# Cooling_control.net
KiCad netlist of a schematic drawn in Altium Designer
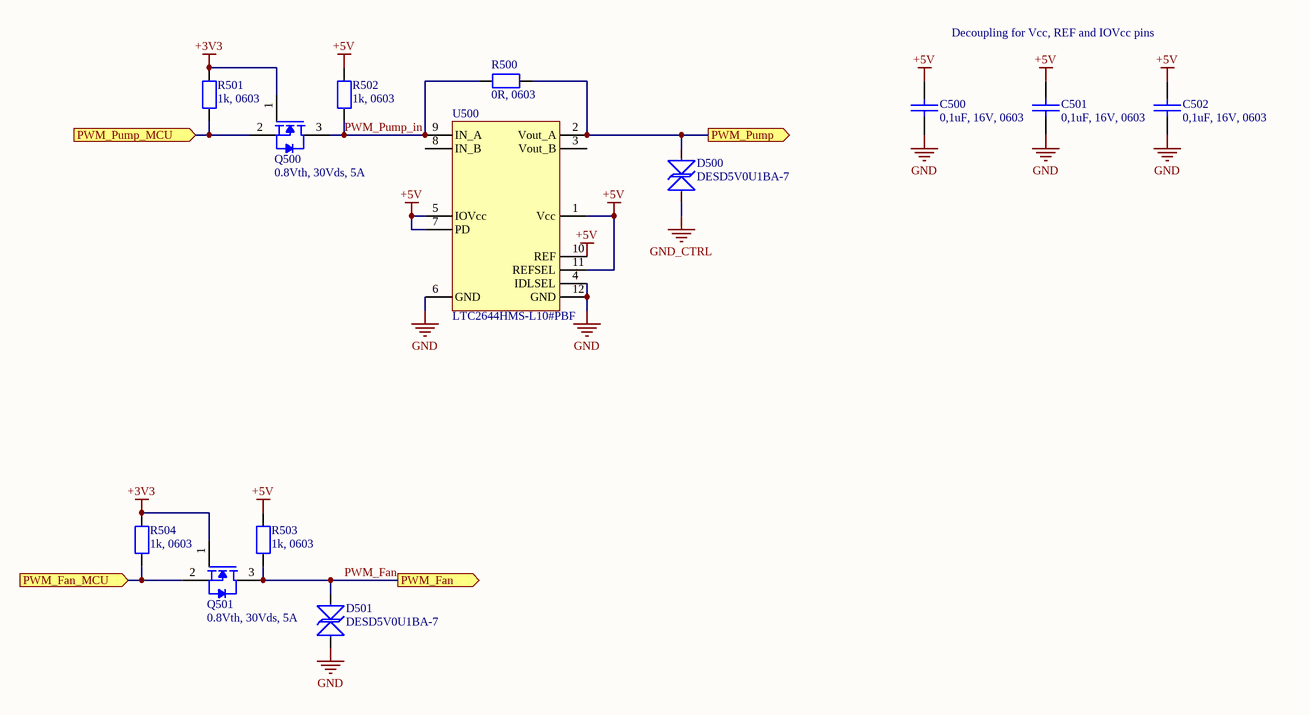
[diagram p0: Cooling_control.SchDoc]

(export (version "E")
  (design (tool "Eeschema 10.0.6"))
  (components
    (comp (ref "C500")
      (value "0,1uF, 16V, 0603")
      (footprint "CAP [0603] 1608")
      (description "Default capacitor part")
      (libsource (lib "Formula Student Team Tallinn (Estonia)") (part "Capacitor"))
    )
    (comp (ref "C501")
      (value "0,1uF, 16V, 0603")
      (footprint "CAP [0603] 1608")
      (description "Default capacitor part")
      (libsource (lib "Formula Student Team Tallinn (Estonia)") (part "Capacitor"))
    )
    (comp (ref "C502")
      (value "0,1uF, 16V, 0603")
      (footprint "CAP [0603] 1608")
      (description "Default capacitor part")
      (libsource (lib "Formula Student Team Tallinn (Estonia)") (part "Capacitor"))
    )
    (comp (ref "D500")
      (value "DESD5V0U1BA-7")
      (footprint "SOD-323")
      (description "Trans Voltage Suppressor Diode, 5V V(RWM), Bidirectional, 1 Element, Silicon")
      (fields (field (name "MANUFACTURER") "Diodes Inc."))
      (libsource (lib "Formula Student Team Tallinn (Estonia)") (part "Diode TVS Bidirectional"))
    )
    (comp (ref "D501")
      (value "DESD5V0U1BA-7")
      (footprint "SOD-323")
      (description "Trans Voltage Suppressor Diode, 5V V(RWM), Bidirectional, 1 Element, Silicon")
      (fields (field (name "MANUFACTURER") "Diodes Inc."))
      (libsource (lib "Formula Student Team Tallinn (Estonia)") (part "Diode TVS Bidirectional"))
    )
    (comp (ref "Q500")
      (value "0.8Vth, 30Vds, 5A")
      (footprint "SOT23-3")
      (description "Small Signal Field-Effect Transistor")
      (fields (field (name "MANUFACTURER PART NUMBER") "IRLML6344TRPBF"))
      (libsource (lib "Formula Student Team Tallinn (Estonia)") (part "MOSFET (NMOS) SOT23-3"))
    )
    (comp (ref "Q501")
      (value "0.8Vth, 30Vds, 5A")
      (footprint "SOT23-3")
      (description "Small Signal Field-Effect Transistor")
      (fields (field (name "MANUFACTURER PART NUMBER") "IRLML6344TRPBF"))
      (libsource (lib "Formula Student Team Tallinn (Estonia)") (part "MOSFET (NMOS) SOT23-3"))
    )
    (comp (ref "R500")
      (value "0R, 0603")
      (footprint "RES [0603] 1608")
      (description "Standard resistor part")
      (libsource (lib "Formula Student Team Tallinn (Estonia)") (part "Resistor"))
    )
    (comp (ref "R501")
      (value "1k, 0603")
      (footprint "RES [0603] 1608")
      (description "Standard resistor part")
      (libsource (lib "Formula Student Team Tallinn (Estonia)") (part "Resistor"))
    )
    (comp (ref "R502")
      (value "1k, 0603")
      (footprint "RES [0603] 1608")
      (description "Standard resistor part")
      (libsource (lib "Formula Student Team Tallinn (Estonia)") (part "Resistor"))
    )
    (comp (ref "R503")
      (value "1k, 0603")
      (footprint "RES [0603] 1608")
      (description "Standard resistor part")
      (libsource (lib "Formula Student Team Tallinn (Estonia)") (part "Resistor"))
    )
    (comp (ref "R504")
      (value "1k, 0603")
      (footprint "RES [0603] 1608")
      (description "Standard resistor part")
      (libsource (lib "Formula Student Team Tallinn (Estonia)") (part "Resistor"))
    )
    (comp (ref "U500")
      (value "LTC2644HMS-L10#PBF")
      (footprint "MSOP-12")
      (description "IC DAC 10-BIT VOUT 12MSOP")
      (fields (field (name "MANUFACTURER") "Mouser"))
      (libsource (lib "Formula Student Team Tallinn (Estonia)") (part "LTC2644HMS-L10#PBF-Symbol-1"))
    )
  )
  (nets
    (net (code "1") (name "+3V3") (class "Default")
      (node (ref "Q500") (pin "1") (pinfunction "G_1") (pintype "passive"))
      (node (ref "Q501") (pin "1") (pinfunction "G_1") (pintype "passive"))
      (node (ref "R501") (pin "2") (pinfunction "2_2") (pintype "passive"))
      (node (ref "R504") (pin "2") (pinfunction "2_2") (pintype "passive"))
    )
    (net (code "2") (name "+5V") (class "Default")
      (node (ref "C500") (pin "1") (pinfunction "1_1") (pintype "passive"))
      (node (ref "C501") (pin "1") (pinfunction "1_1") (pintype "passive"))
      (node (ref "C502") (pin "1") (pinfunction "1_1") (pintype "passive"))
      (node (ref "R502") (pin "2") (pinfunction "2_2") (pintype "passive"))
      (node (ref "R503") (pin "2") (pinfunction "2_2") (pintype "passive"))
      (node (ref "U500") (pin "1") (pinfunction "Vcc_1") (pintype "passive"))
      (node (ref "U500") (pin "10") (pinfunction "REF_10") (pintype "passive"))
      (node (ref "U500") (pin "11") (pinfunction "REFSEL_11") (pintype "passive"))
      (node (ref "U500") (pin "5") (pinfunction "IOVcc_5") (pintype "passive"))
      (node (ref "U500") (pin "7") (pinfunction "PD_7") (pintype "passive"))
    )
    (net (code "3") (name "/PWM_Fan") (class "Default")
      (node (ref "D501") (pin "1") (pinfunction "1_1") (pintype "passive"))
      (node (ref "Q501") (pin "3") (pinfunction "D_3") (pintype "passive"))
      (node (ref "R503") (pin "1") (pinfunction "1_1") (pintype "passive"))
    )
    (net (code "4") (name "/PWM_Fan_MCU") (class "Default")
      (node (ref "Q501") (pin "2") (pinfunction "S_2") (pintype "passive"))
      (node (ref "R504") (pin "1") (pinfunction "1_1") (pintype "passive"))
    )
    (net (code "5") (name "/PWM_Pump") (class "Default")
      (node (ref "D500") (pin "1") (pinfunction "1_1") (pintype "passive"))
      (node (ref "R500") (pin "2") (pinfunction "2_2") (pintype "passive"))
      (node (ref "U500") (pin "2") (pinfunction "Vout_A_2") (pintype "passive"))
    )
    (net (code "6") (name "/PWM_Pump_MCU") (class "Default")
      (node (ref "Q500") (pin "2") (pinfunction "S_2") (pintype "passive"))
      (node (ref "R501") (pin "1") (pinfunction "1_1") (pintype "passive"))
    )
    (net (code "7") (name "/PWM_Pump_in") (class "Default")
      (node (ref "Q500") (pin "3") (pinfunction "D_3") (pintype "passive"))
      (node (ref "R500") (pin "1") (pinfunction "1_1") (pintype "passive"))
      (node (ref "R502") (pin "1") (pinfunction "1_1") (pintype "passive"))
      (node (ref "U500") (pin "9") (pinfunction "IN_A_9") (pintype "passive"))
    )
    (net (code "8") (name "GND") (class "Default")
      (node (ref "C500") (pin "2") (pinfunction "2_2") (pintype "passive"))
      (node (ref "C501") (pin "2") (pinfunction "2_2") (pintype "passive"))
      (node (ref "C502") (pin "2") (pinfunction "2_2") (pintype "passive"))
      (node (ref "D501") (pin "2") (pinfunction "2_2") (pintype "passive"))
      (node (ref "U500") (pin "12") (pinfunction "GND_12") (pintype "passive"))
      (node (ref "U500") (pin "4") (pinfunction "IDLSEL_4") (pintype "passive"))
      (node (ref "U500") (pin "6") (pinfunction "GND_6") (pintype "passive"))
    )
    (net (code "9") (name "GND_CTRL") (class "Default")
      (node (ref "D500") (pin "2") (pinfunction "2_2") (pintype "passive"))
    )
    (net (code "10") (name "unconnected-(U500-IN_B-Pad8)") (class "Default")
      (node (ref "U500") (pin "8") (pinfunction "IN_B_8") (pintype "passive"))
    )
    (net (code "11") (name "unconnected-(U500-Vout_B-Pad3)") (class "Default")
      (node (ref "U500") (pin "3") (pinfunction "Vout_B_3") (pintype "passive"))
    )
  )
)
